# ADC_CPLDV9.net
KiCad netlist of a schematic drawn in EAGLE
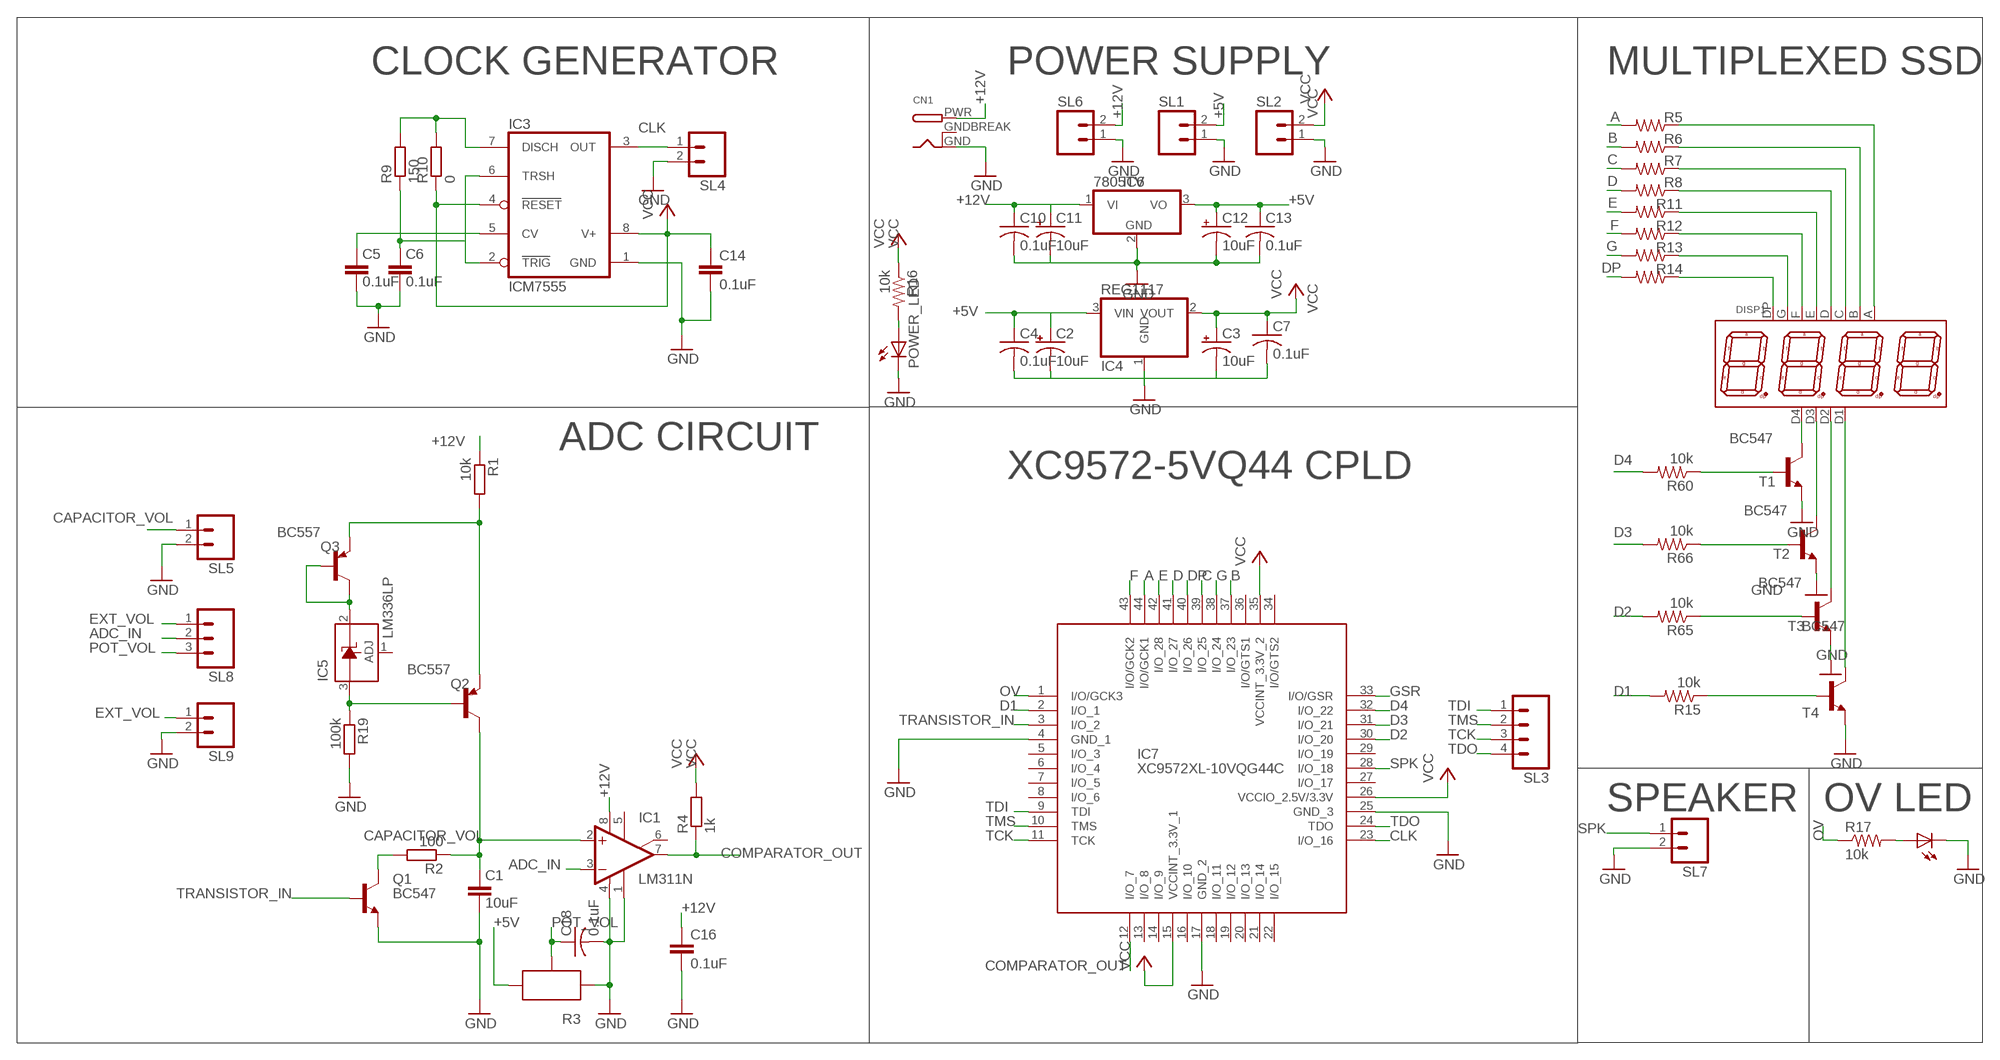
[diagram p0: schematic, sheet 1]

(export (version "E")
  (design (tool "Eeschema 10.0.6"))
  (components
    (comp (ref "C1")
      (value "10uF")
      (footprint "eagle-import:C025-025X050")
      (libsource (lib "eagle-import") (part "C-EU025-025X050"))
    )
    (comp (ref "C2")
      (value "10uF")
      (footprint "eagle-import:B_3528-21R")
      (libsource (lib "eagle-import") (part "CPOL-USB/3528-21R"))
    )
    (comp (ref "C3")
      (value "10uF")
      (footprint "eagle-import:B_3528-21R")
      (libsource (lib "eagle-import") (part "CPOL-USB/3528-21R"))
    )
    (comp (ref "C4")
      (value "0.1uF")
      (footprint "eagle-import:C0805")
      (libsource (lib "eagle-import") (part "C-USC0805"))
    )
    (comp (ref "C5")
      (value "0.1uF")
      (footprint "eagle-import:C025-024X044")
      (libsource (lib "eagle-import") (part "C-EU025-024X044"))
    )
    (comp (ref "C6")
      (value "0.1uF")
      (footprint "eagle-import:C025-024X044")
      (libsource (lib "eagle-import") (part "C-EU025-024X044"))
    )
    (comp (ref "C7")
      (value "0.1uF")
      (footprint "eagle-import:C0805")
      (libsource (lib "eagle-import") (part "C-USC0805"))
    )
    (comp (ref "C10")
      (value "0.1uF")
      (footprint "eagle-import:C0805")
      (libsource (lib "eagle-import") (part "C-USC0805"))
    )
    (comp (ref "C11")
      (value "10uF")
      (footprint "eagle-import:B_3528-21R")
      (libsource (lib "eagle-import") (part "CPOL-USB/3528-21R"))
    )
    (comp (ref "C12")
      (value "10uF")
      (footprint "eagle-import:B_3528-21R")
      (libsource (lib "eagle-import") (part "CPOL-USB/3528-21R"))
    )
    (comp (ref "C13")
      (value "0.1uF")
      (footprint "eagle-import:C0805")
      (libsource (lib "eagle-import") (part "C-USC0805"))
    )
    (comp (ref "C14")
      (value "0.1uF")
      (footprint "eagle-import:C025-025X050")
      (libsource (lib "eagle-import") (part "C-EU025-025X050"))
    )
    (comp (ref "C16")
      (value "0.1uF")
      (footprint "eagle-import:C025-025X050")
      (libsource (lib "eagle-import") (part "C-EU025-025X050"))
    )
    (comp (ref "C18")
      (value "0.1uF")
      (footprint "eagle-import:C0805")
      (libsource (lib "eagle-import") (part "C-USC0805"))
    )
    (comp (ref "CN1")
      (value "DCBARRELPTH")
      (footprint "eagle-import:DCJACK_2MM_PTH")
      (libsource (lib "eagle-import") (part "DCBARRELPTH"))
    )
    (comp (ref "DISP1")
      (value "7-SEG_4D_0.36")
      (footprint "eagle-import:7SEG-4DIG")
      (libsource (lib "eagle-import") (part "7-SEG_4D_0.36"))
    )
    (comp (ref "IC1")
      (value "LM311N")
      (footprint "eagle-import:DIL08")
      (libsource (lib "eagle-import") (part "LM311N"))
    )
    (comp (ref "IC3")
      (value "ICM7555")
      (footprint "eagle-import:DIL08")
      (fields (field (name "MF") "MAXIM") (field (name "MPN") "ICM7555IPA+"))
      (libsource (lib "eagle-import") (part "ICM7555"))
    )
    (comp (ref "IC4")
      (value "REG1117")
      (footprint "eagle-import:SOT223")
      (libsource (lib "eagle-import") (part "REG1117"))
    )
    (comp (ref "IC5")
      (value "LM336LP")
      (footprint "eagle-import:TO92")
      (libsource (lib "eagle-import") (part "LM336LP"))
    )
    (comp (ref "IC6")
      (value "7805TV")
      (footprint "eagle-import:TO220V")
      (libsource (lib "eagle-import") (part "78TV05"))
    )
    (comp (ref "IC7")
      (value "XC9572XL-10VQG44C")
      (footprint "eagle-import:44_PIN_BOB")
      (libsource (lib "eagle-import") (part "XC9572XL-10VQG44C"))
    )
    (comp (ref "POWER_LED")
      (value "LED3MM")
      (footprint "eagle-import:LED3MM")
      (libsource (lib "eagle-import") (part "LED3MM"))
    )
    (comp (ref "POWER_LED1")
      (value "LED3MM")
      (footprint "eagle-import:LED3MM")
      (libsource (lib "eagle-import") (part "LED3MM"))
    )
    (comp (ref "Q1")
      (value "BC547")
      (footprint "eagle-import:TO92")
      (libsource (lib "eagle-import") (part "transistor_402_BC547"))
    )
    (comp (ref "Q2")
      (value "BC557")
      (footprint "eagle-import:TO92")
      (libsource (lib "eagle-import") (part "BC557"))
    )
    (comp (ref "Q3")
      (value "BC557")
      (footprint "eagle-import:TO92")
      (libsource (lib "eagle-import") (part "BC557"))
    )
    (comp (ref "R1")
      (value "10k")
      (footprint "eagle-import:0204_7")
      (libsource (lib "eagle-import") (part "R-EU_0204/7"))
    )
    (comp (ref "R2")
      (value "100")
      (footprint "eagle-import:0204_7")
      (libsource (lib "eagle-import") (part "R-EU_0204/7"))
    )
    (comp (ref "R3")
      (value "POTNORMAL")
      (footprint "eagle-import:RJ9W")
      (libsource (lib "eagle-import") (part "POTNORMAL"))
    )
    (comp (ref "R4")
      (value "1k")
      (footprint "eagle-import:0207_10")
      (libsource (lib "eagle-import") (part "R-EU_0207/10"))
    )
    (comp (ref "R5")
      (value "330")
      (footprint "eagle-import:0207_7")
      (libsource (lib "eagle-import") (part "R-US_0207/7"))
    )
    (comp (ref "R6")
      (value "330")
      (footprint "eagle-import:0207_7")
      (libsource (lib "eagle-import") (part "R-US_0207/7"))
    )
    (comp (ref "R7")
      (value "330")
      (footprint "eagle-import:0207_7")
      (libsource (lib "eagle-import") (part "R-US_0207/7"))
    )
    (comp (ref "R8")
      (value "1k")
      (footprint "eagle-import:0207_7")
      (libsource (lib "eagle-import") (part "R-US_0207/7"))
    )
    (comp (ref "R9")
      (value "150")
      (footprint "eagle-import:0204_7")
      (libsource (lib "eagle-import") (part "R-EU_0204/7"))
    )
    (comp (ref "R10")
      (value "0")
      (footprint "eagle-import:0204_7")
      (libsource (lib "eagle-import") (part "R-EU_0204/7"))
    )
    (comp (ref "R11")
      (value "330")
      (footprint "eagle-import:0207_7")
      (libsource (lib "eagle-import") (part "R-US_0207/7"))
    )
    (comp (ref "R12")
      (value "330")
      (footprint "eagle-import:0207_7")
      (libsource (lib "eagle-import") (part "R-US_0207/7"))
    )
    (comp (ref "R13")
      (value "330")
      (footprint "eagle-import:0207_7")
      (libsource (lib "eagle-import") (part "R-US_0207/7"))
    )
    (comp (ref "R14")
      (value "330")
      (footprint "eagle-import:0207_7")
      (libsource (lib "eagle-import") (part "R-US_0207/7"))
    )
    (comp (ref "R15")
      (value "10k")
      (footprint "eagle-import:0207_7")
      (libsource (lib "eagle-import") (part "R-US_0207/7"))
    )
    (comp (ref "R16")
      (value "10k")
      (footprint "eagle-import:0207_7")
      (libsource (lib "eagle-import") (part "R-US_0207/7"))
    )
    (comp (ref "R17")
      (value "10k")
      (footprint "eagle-import:0207_7")
      (libsource (lib "eagle-import") (part "R-US_0207/7"))
    )
    (comp (ref "R19")
      (value "100k")
      (footprint "eagle-import:0204_7")
      (libsource (lib "eagle-import") (part "R-EU_0204/7"))
    )
    (comp (ref "R60")
      (value "10k")
      (footprint "eagle-import:0207_7")
      (libsource (lib "eagle-import") (part "R-US_0207/7"))
    )
    (comp (ref "R65")
      (value "10k")
      (footprint "eagle-import:0207_7")
      (libsource (lib "eagle-import") (part "R-US_0207/7"))
    )
    (comp (ref "R66")
      (value "10k")
      (footprint "eagle-import:0207_7")
      (libsource (lib "eagle-import") (part "R-US_0207/7"))
    )
    (comp (ref "SL1")
      (value "M02")
      (footprint "eagle-import:02P")
      (libsource (lib "eagle-import") (part "M02"))
    )
    (comp (ref "SL2")
      (value "M02")
      (footprint "eagle-import:02P")
      (libsource (lib "eagle-import") (part "M02"))
    )
    (comp (ref "SL3")
      (value "M04")
      (footprint "eagle-import:04P")
      (libsource (lib "eagle-import") (part "M04"))
    )
    (comp (ref "SL4")
      (value "M02")
      (footprint "eagle-import:02P")
      (libsource (lib "eagle-import") (part "M02"))
    )
    (comp (ref "SL5")
      (value "M02")
      (footprint "eagle-import:02P")
      (libsource (lib "eagle-import") (part "M02"))
    )
    (comp (ref "SL6")
      (value "M02")
      (footprint "eagle-import:02P")
      (libsource (lib "eagle-import") (part "M02"))
    )
    (comp (ref "SL7")
      (value "M02")
      (footprint "eagle-import:02P")
      (libsource (lib "eagle-import") (part "M02"))
    )
    (comp (ref "SL8")
      (value "M03")
      (footprint "eagle-import:03P")
      (libsource (lib "eagle-import") (part "M03"))
    )
    (comp (ref "SL9")
      (value "M02")
      (footprint "eagle-import:02P")
      (libsource (lib "eagle-import") (part "M02"))
    )
    (comp (ref "T1")
      (value "BC547")
      (footprint "eagle-import:TO92")
      (libsource (lib "eagle-import") (part "BC547"))
    )
    (comp (ref "T2")
      (value "BC547")
      (footprint "eagle-import:TO92")
      (libsource (lib "eagle-import") (part "BC547"))
    )
    (comp (ref "T3")
      (value "BC547")
      (footprint "eagle-import:TO92")
      (libsource (lib "eagle-import") (part "BC547"))
    )
    (comp (ref "T4")
      (value "BC547")
      (footprint "eagle-import:TO92")
      (libsource (lib "eagle-import") (part "BC547"))
    )
  )
  (nets
    (net (code "1") (name "/+5V") (class "Default")
      (node (ref "C12") (pin "+") (pinfunction "+_+") (pintype "passive"))
      (node (ref "C13") (pin "1") (pinfunction "1_1") (pintype "passive"))
      (node (ref "C2") (pin "+") (pinfunction "+_+") (pintype "passive"))
      (node (ref "C4") (pin "1") (pinfunction "1_1") (pintype "passive"))
      (node (ref "IC4") (pin "3") (pinfunction "VIN_3") (pintype "input"))
      (node (ref "IC6") (pin "3") (pinfunction "VO_3") (pintype "passive"))
      (node (ref "R3") (pin "A") (pinfunction "A_A") (pintype "passive"))
      (node (ref "SL1") (pin "2") (pinfunction "2_2") (pintype "passive"))
    )
    (net (code "2") (name "/+12V") (class "Default")
      (node (ref "C10") (pin "1") (pinfunction "1_1") (pintype "passive"))
      (node (ref "C11") (pin "+") (pinfunction "+_+") (pintype "passive"))
      (node (ref "C16") (pin "1") (pinfunction "1_1") (pintype "passive"))
      (node (ref "CN1") (pin "PWR") (pinfunction "PWR_PWR") (pintype "power_in"))
      (node (ref "IC1") (pin "8") (pinfunction "V+_8") (pintype "power_in"))
      (node (ref "IC6") (pin "1") (pinfunction "VI_1") (pintype "input"))
      (node (ref "R1") (pin "1") (pinfunction "1_1") (pintype "passive"))
      (node (ref "SL6") (pin "2") (pinfunction "2_2") (pintype "passive"))
    )
    (net (code "3") (name "/A") (class "Default")
      (node (ref "IC7") (pin "44") (pinfunction "I/O/GCK1_44") (pintype "bidirectional"))
      (node (ref "R5") (pin "2") (pinfunction "2_2") (pintype "passive"))
    )
    (net (code "4") (name "/ADC_IN") (class "Default")
      (node (ref "IC1") (pin "3") (pinfunction "-IN_3") (pintype "input"))
      (node (ref "SL8") (pin "2") (pinfunction "2_2") (pintype "passive"))
    )
    (net (code "5") (name "/B") (class "Default")
      (node (ref "IC7") (pin "37") (pinfunction "I/O_23_37") (pintype "bidirectional"))
      (node (ref "R6") (pin "2") (pinfunction "2_2") (pintype "passive"))
    )
    (net (code "6") (name "/C") (class "Default")
      (node (ref "IC7") (pin "39") (pinfunction "I/O_25_39") (pintype "bidirectional"))
      (node (ref "R7") (pin "2") (pinfunction "2_2") (pintype "passive"))
    )
    (net (code "7") (name "/CAPACITOR_VOL") (class "Default")
      (node (ref "C1") (pin "1") (pinfunction "1_1") (pintype "passive"))
      (node (ref "IC1") (pin "2") (pinfunction "+IN_2") (pintype "input"))
      (node (ref "Q2") (pin "3") (pinfunction "C_3") (pintype "passive"))
      (node (ref "R2") (pin "1") (pinfunction "1_1") (pintype "passive"))
      (node (ref "SL5") (pin "1") (pinfunction "1_1") (pintype "passive"))
    )
    (net (code "8") (name "/CLK") (class "Default")
      (node (ref "IC3") (pin "3") (pinfunction "OUT_3") (pintype "output"))
      (node (ref "IC7") (pin "23") (pinfunction "I/O_16_23") (pintype "bidirectional"))
      (node (ref "SL4") (pin "1") (pinfunction "1_1") (pintype "passive"))
    )
    (net (code "9") (name "/COMPARATOR_OUT") (class "Default")
      (node (ref "IC1") (pin "7") (pinfunction "OUT_7") (pintype "output"))
      (node (ref "IC7") (pin "12") (pinfunction "I/O_7_12") (pintype "bidirectional"))
      (node (ref "R4") (pin "1") (pinfunction "1_1") (pintype "passive"))
    )
    (net (code "10") (name "/D") (class "Default")
      (node (ref "IC7") (pin "41") (pinfunction "I/O_27_41") (pintype "bidirectional"))
      (node (ref "R8") (pin "2") (pinfunction "2_2") (pintype "passive"))
    )
    (net (code "11") (name "/D1") (class "Default")
      (node (ref "IC7") (pin "2") (pinfunction "I/O_1_2") (pintype "bidirectional"))
      (node (ref "R15") (pin "2") (pinfunction "2_2") (pintype "passive"))
    )
    (net (code "12") (name "/D2") (class "Default")
      (node (ref "IC7") (pin "30") (pinfunction "I/O_20_30") (pintype "bidirectional"))
      (node (ref "R65") (pin "2") (pinfunction "2_2") (pintype "passive"))
    )
    (net (code "13") (name "/D3") (class "Default")
      (node (ref "IC7") (pin "31") (pinfunction "I/O_21_31") (pintype "bidirectional"))
      (node (ref "R66") (pin "2") (pinfunction "2_2") (pintype "passive"))
    )
    (net (code "14") (name "/D4") (class "Default")
      (node (ref "IC7") (pin "32") (pinfunction "I/O_22_32") (pintype "bidirectional"))
      (node (ref "R60") (pin "2") (pinfunction "2_2") (pintype "passive"))
    )
    (net (code "15") (name "/DP") (class "Default")
      (node (ref "IC7") (pin "40") (pinfunction "I/O_26_40") (pintype "bidirectional"))
      (node (ref "R14") (pin "2") (pinfunction "2_2") (pintype "passive"))
    )
    (net (code "16") (name "/E") (class "Default")
      (node (ref "IC7") (pin "42") (pinfunction "I/O_28_42") (pintype "bidirectional"))
      (node (ref "R11") (pin "2") (pinfunction "2_2") (pintype "passive"))
    )
    (net (code "17") (name "/EXT_VOL") (class "Default")
      (node (ref "SL8") (pin "1") (pinfunction "1_1") (pintype "passive"))
      (node (ref "SL9") (pin "1") (pinfunction "1_1") (pintype "passive"))
    )
    (net (code "18") (name "/F") (class "Default")
      (node (ref "IC7") (pin "43") (pinfunction "I/O/GCK2_43") (pintype "bidirectional"))
      (node (ref "R12") (pin "2") (pinfunction "2_2") (pintype "passive"))
    )
    (net (code "19") (name "/G") (class "Default")
      (node (ref "IC7") (pin "38") (pinfunction "I/O_24_38") (pintype "bidirectional"))
      (node (ref "R13") (pin "2") (pinfunction "2_2") (pintype "passive"))
    )
    (net (code "20") (name "/GNDBREAK") (class "Default")
      (node (ref "CN1") (pin "GNDBREAK") (pinfunction "GNDBREAK_GNDBREAK") (pintype "power_in"))
    )
    (net (code "21") (name "/GSR") (class "Default")
      (node (ref "IC7") (pin "33") (pinfunction "I/O/GSR_33") (pintype "bidirectional"))
    )
    (net (code "22") (name "/OV") (class "Default")
      (node (ref "IC7") (pin "1") (pinfunction "I/O/GCK3_1") (pintype "bidirectional"))
      (node (ref "R17") (pin "1") (pinfunction "1_1") (pintype "passive"))
    )
    (net (code "23") (name "/POT_VOL") (class "Default")
      (node (ref "C18") (pin "1") (pinfunction "1_1") (pintype "passive"))
      (node (ref "R3") (pin "S") (pinfunction "S_S") (pintype "passive"))
      (node (ref "SL8") (pin "3") (pinfunction "3_3") (pintype "passive"))
    )
    (net (code "24") (name "/SPK") (class "Default")
      (node (ref "IC7") (pin "28") (pinfunction "I/O_18_28") (pintype "bidirectional"))
      (node (ref "SL7") (pin "1") (pinfunction "1_1") (pintype "passive"))
    )
    (net (code "25") (name "/TCK") (class "Default")
      (node (ref "IC7") (pin "11") (pinfunction "TCK_11") (pintype "bidirectional"))
      (node (ref "SL3") (pin "3") (pinfunction "3_3") (pintype "passive"))
    )
    (net (code "26") (name "/TDI") (class "Default")
      (node (ref "IC7") (pin "9") (pinfunction "TDI_9") (pintype "input"))
      (node (ref "SL3") (pin "1") (pinfunction "1_1") (pintype "passive"))
    )
    (net (code "27") (name "/TDO") (class "Default")
      (node (ref "IC7") (pin "24") (pinfunction "TDO_24") (pintype "output"))
      (node (ref "SL3") (pin "4") (pinfunction "4_4") (pintype "passive"))
    )
    (net (code "28") (name "/TMS") (class "Default")
      (node (ref "IC7") (pin "10") (pinfunction "TMS_10") (pintype "bidirectional"))
      (node (ref "SL3") (pin "2") (pinfunction "2_2") (pintype "passive"))
    )
    (net (code "29") (name "/TRANSISTOR_IN") (class "Default")
      (node (ref "IC7") (pin "3") (pinfunction "I/O_2_3") (pintype "bidirectional"))
      (node (ref "Q1") (pin "2") (pinfunction "B_2") (pintype "passive"))
    )
    (net (code "30") (name "GND") (class "Default")
      (node (ref "C1") (pin "2") (pinfunction "2_2") (pintype "passive"))
      (node (ref "C10") (pin "2") (pinfunction "2_2") (pintype "passive"))
      (node (ref "C11") (pin "-") (pinfunction "-_-") (pintype "passive"))
      (node (ref "C12") (pin "-") (pinfunction "-_-") (pintype "passive"))
      (node (ref "C13") (pin "2") (pinfunction "2_2") (pintype "passive"))
      (node (ref "C14") (pin "2") (pinfunction "2_2") (pintype "passive"))
      (node (ref "C16") (pin "2") (pinfunction "2_2") (pintype "passive"))
      (node (ref "C18") (pin "2") (pinfunction "2_2") (pintype "passive"))
      (node (ref "C2") (pin "-") (pinfunction "-_-") (pintype "passive"))
      (node (ref "C3") (pin "-") (pinfunction "-_-") (pintype "passive"))
      (node (ref "C4") (pin "2") (pinfunction "2_2") (pintype "passive"))
      (node (ref "C5") (pin "2") (pinfunction "2_2") (pintype "passive"))
      (node (ref "C6") (pin "2") (pinfunction "2_2") (pintype "passive"))
      (node (ref "C7") (pin "2") (pinfunction "2_2") (pintype "passive"))
      (node (ref "CN1") (pin "GND") (pinfunction "GND_GND") (pintype "power_in"))
      (node (ref "IC1") (pin "1") (pinfunction "GND_1") (pintype "passive"))
      (node (ref "IC1") (pin "4") (pinfunction "V-_4") (pintype "power_in"))
      (node (ref "IC3") (pin "1") (pinfunction "GND_1") (pintype "power_in"))
      (node (ref "IC4") (pin "1") (pinfunction "GND_1") (pintype "power_in"))
      (node (ref "IC6") (pin "2") (pinfunction "GND_2") (pintype "passive"))
      (node (ref "IC7") (pin "17") (pinfunction "GND_2_17") (pintype "power_in"))
      (node (ref "IC7") (pin "25") (pinfunction "GND_3_25") (pintype "power_in"))
      (node (ref "IC7") (pin "4") (pinfunction "GND_1_4") (pintype "power_in"))
      (node (ref "POWER_LED") (pin "K") (pinfunction "C_K") (pintype "passive"))
      (node (ref "POWER_LED1") (pin "K") (pinfunction "C_K") (pintype "passive"))
      (node (ref "Q1") (pin "1") (pinfunction "E_1") (pintype "passive"))
      (node (ref "R19") (pin "2") (pinfunction "2_2") (pintype "passive"))
      (node (ref "R3") (pin "E") (pinfunction "E_E") (pintype "passive"))
      (node (ref "SL1") (pin "1") (pinfunction "1_1") (pintype "passive"))
      (node (ref "SL2") (pin "1") (pinfunction "1_1") (pintype "passive"))
      (node (ref "SL4") (pin "2") (pinfunction "2_2") (pintype "passive"))
      (node (ref "SL5") (pin "2") (pinfunction "2_2") (pintype "passive"))
      (node (ref "SL6") (pin "1") (pinfunction "1_1") (pintype "passive"))
      (node (ref "SL7") (pin "2") (pinfunction "2_2") (pintype "passive"))
      (node (ref "SL9") (pin "2") (pinfunction "2_2") (pintype "passive"))
      (node (ref "T1") (pin "1") (pinfunction "E_1") (pintype "passive"))
      (node (ref "T2") (pin "1") (pinfunction "E_1") (pintype "passive"))
      (node (ref "T3") (pin "1") (pinfunction "E_1") (pintype "passive"))
      (node (ref "T4") (pin "1") (pinfunction "E_1") (pintype "passive"))
    )
    (net (code "31") (name "Net-(DISP1-PadA)") (class "Default")
      (node (ref "DISP1") (pin "A") (pinfunction "A_A") (pintype "bidirectional"))
      (node (ref "R5") (pin "1") (pinfunction "1_1") (pintype "passive"))
    )
    (net (code "32") (name "Net-(DISP1-PadB)") (class "Default")
      (node (ref "DISP1") (pin "B") (pinfunction "B_B") (pintype "bidirectional"))
      (node (ref "R6") (pin "1") (pinfunction "1_1") (pintype "passive"))
    )
    (net (code "33") (name "Net-(DISP1-PadC)") (class "Default")
      (node (ref "DISP1") (pin "C") (pinfunction "C_C") (pintype "bidirectional"))
      (node (ref "R7") (pin "1") (pinfunction "1_1") (pintype "passive"))
    )
    (net (code "34") (name "Net-(DISP1-PadD)") (class "Default")
      (node (ref "DISP1") (pin "D") (pinfunction "D_D") (pintype "bidirectional"))
      (node (ref "R8") (pin "1") (pinfunction "1_1") (pintype "passive"))
    )
    (net (code "35") (name "Net-(DISP1-PadDP)") (class "Default")
      (node (ref "DISP1") (pin "DP") (pinfunction "DP_DP") (pintype "bidirectional"))
      (node (ref "R14") (pin "1") (pinfunction "1_1") (pintype "passive"))
    )
    (net (code "36") (name "Net-(DISP1-PadE)") (class "Default")
      (node (ref "DISP1") (pin "E") (pinfunction "E_E") (pintype "bidirectional"))
      (node (ref "R11") (pin "1") (pinfunction "1_1") (pintype "passive"))
    )
    (net (code "37") (name "Net-(DISP1-PadF)") (class "Default")
      (node (ref "DISP1") (pin "F") (pinfunction "F_F") (pintype "bidirectional"))
      (node (ref "R12") (pin "1") (pinfunction "1_1") (pintype "passive"))
    )
    (net (code "38") (name "Net-(DISP1-PadG)") (class "Default")
      (node (ref "DISP1") (pin "G") (pinfunction "G_G") (pintype "bidirectional"))
      (node (ref "R13") (pin "1") (pinfunction "1_1") (pintype "passive"))
    )
    (net (code "39") (name "Net-(IC3-CV)") (class "Default")
      (node (ref "C5") (pin "1") (pinfunction "1_1") (pintype "passive"))
      (node (ref "IC3") (pin "5") (pinfunction "CV_5") (pintype "passive"))
    )
    (net (code "40") (name "Net-(IC3-DISCH)") (class "Default")
      (node (ref "IC3") (pin "7") (pinfunction "DISCH_7") (pintype "input"))
      (node (ref "R10") (pin "2") (pinfunction "2_2") (pintype "passive"))
      (node (ref "R9") (pin "2") (pinfunction "2_2") (pintype "passive"))
    )
    (net (code "41") (name "Net-(IC3-TRIG)") (class "Default")
      (node (ref "C6") (pin "1") (pinfunction "1_1") (pintype "passive"))
      (node (ref "IC3") (pin "2") (pinfunction "TRIG_2") (pintype "bidirectional"))
      (node (ref "IC3") (pin "6") (pinfunction "TRSH_6") (pintype "input"))
      (node (ref "R9") (pin "1") (pinfunction "1_1") (pintype "passive"))
    )
    (net (code "42") (name "Net-(IC5-A)") (class "Default")
      (node (ref "IC5") (pin "3") (pinfunction "A_3") (pintype "input"))
      (node (ref "Q2") (pin "2") (pinfunction "B_2") (pintype "passive"))
      (node (ref "R19") (pin "1") (pinfunction "1_1") (pintype "passive"))
    )
    (net (code "43") (name "Net-(IC5-C)") (class "Default")
      (node (ref "IC5") (pin "2") (pinfunction "C_2") (pintype "passive"))
      (node (ref "Q3") (pin "2") (pinfunction "B_2") (pintype "passive"))
      (node (ref "Q3") (pin "3") (pinfunction "C_3") (pintype "passive"))
    )
    (net (code "44") (name "Net-(POWER_LED-PadA)") (class "Default")
      (node (ref "POWER_LED") (pin "A") (pinfunction "A_A") (pintype "passive"))
      (node (ref "R16") (pin "2") (pinfunction "2_2") (pintype "passive"))
    )
    (net (code "45") (name "Net-(POWER_LED1-PadA)") (class "Default")
      (node (ref "POWER_LED1") (pin "A") (pinfunction "A_A") (pintype "passive"))
      (node (ref "R17") (pin "2") (pinfunction "2_2") (pintype "passive"))
    )
    (net (code "46") (name "Net-(Q1-C)") (class "Default")
      (node (ref "Q1") (pin "3") (pinfunction "C_3") (pintype "passive"))
      (node (ref "R2") (pin "2") (pinfunction "2_2") (pintype "passive"))
    )
    (net (code "47") (name "Net-(Q2-E)") (class "Default")
      (node (ref "Q2") (pin "1") (pinfunction "E_1") (pintype "passive"))
      (node (ref "Q3") (pin "1") (pinfunction "E_1") (pintype "passive"))
      (node (ref "R1") (pin "2") (pinfunction "2_2") (pintype "passive"))
    )
    (net (code "48") (name "Net-(T1-B)") (class "Default")
      (node (ref "R60") (pin "1") (pinfunction "1_1") (pintype "passive"))
      (node (ref "T1") (pin "2") (pinfunction "B_2") (pintype "passive"))
    )
    (net (code "49") (name "Net-(T1-C)") (class "Default")
      (node (ref "DISP1") (pin "D4") (pinfunction "D4_D4") (pintype "bidirectional"))
      (node (ref "T1") (pin "3") (pinfunction "C_3") (pintype "passive"))
    )
    (net (code "50") (name "Net-(T2-B)") (class "Default")
      (node (ref "R66") (pin "1") (pinfunction "1_1") (pintype "passive"))
      (node (ref "T2") (pin "2") (pinfunction "B_2") (pintype "passive"))
    )
    (net (code "51") (name "Net-(T2-C)") (class "Default")
      (node (ref "DISP1") (pin "D3") (pinfunction "D3_D3") (pintype "bidirectional"))
      (node (ref "T2") (pin "3") (pinfunction "C_3") (pintype "passive"))
    )
    (net (code "52") (name "Net-(T3-B)") (class "Default")
      (node (ref "R65") (pin "1") (pinfunction "1_1") (pintype "passive"))
      (node (ref "T3") (pin "2") (pinfunction "B_2") (pintype "passive"))
    )
    (net (code "53") (name "Net-(T3-C)") (class "Default")
      (node (ref "DISP1") (pin "D2") (pinfunction "D2_D2") (pintype "bidirectional"))
      (node (ref "T3") (pin "3") (pinfunction "C_3") (pintype "passive"))
    )
    (net (code "54") (name "Net-(T4-B)") (class "Default")
      (node (ref "R15") (pin "1") (pinfunction "1_1") (pintype "passive"))
      (node (ref "T4") (pin "2") (pinfunction "B_2") (pintype "passive"))
    )
    (net (code "55") (name "Net-(T4-C)") (class "Default")
      (node (ref "DISP1") (pin "D1") (pinfunction "D1_D1") (pintype "bidirectional"))
      (node (ref "T4") (pin "3") (pinfunction "C_3") (pintype "passive"))
    )
    (net (code "56") (name "VCC") (class "Default")
      (node (ref "C14") (pin "1") (pinfunction "1_1") (pintype "passive"))
      (node (ref "C3") (pin "+") (pinfunction "+_+") (pintype "passive"))
      (node (ref "C7") (pin "1") (pinfunction "1_1") (pintype "passive"))
      (node (ref "IC3") (pin "4") (pinfunction "RESET_4") (pintype "input"))
      (node (ref "IC3") (pin "8") (pinfunction "V+_8") (pintype "power_in"))
      (node (ref "IC4") (pin "2") (pinfunction "VOUT_2") (pintype "output"))
      (node (ref "IC7") (pin "15") (pinfunction "VCCINT_3.3V_1_15") (pintype "power_in"))
      (node (ref "IC7") (pin "26") (pinfunction "VCCIO_2.5V/3.3V_26") (pintype "power_in"))
      (node (ref "IC7") (pin "35") (pinfunction "VCCINT_3.3V_2_35") (pintype "power_in"))
      (node (ref "R10") (pin "1") (pinfunction "1_1") (pintype "passive"))
      (node (ref "R16") (pin "1") (pinfunction "1_1") (pintype "passive"))
      (node (ref "R4") (pin "2") (pinfunction "2_2") (pintype "passive"))
      (node (ref "SL2") (pin "2") (pinfunction "2_2") (pintype "passive"))
    )
    (net (code "57") (name "unconnected-(IC1-ON-Pad5)") (class "Default")
      (node (ref "IC1") (pin "5") (pinfunction "ON_5") (pintype "passive"))
    )
    (net (code "58") (name "unconnected-(IC1-ON{slash}STR-Pad6)") (class "Default")
      (node (ref "IC1") (pin "6") (pinfunction "ON/STR_6") (pintype "passive"))
    )
    (net (code "59") (name "unconnected-(IC5-ADJ-Pad1)") (class "Default")
      (node (ref "IC5") (pin "1") (pinfunction "ADJ_1") (pintype "input"))
    )
    (net (code "60") (name "unconnected-(IC7-I{slash}O_3-Pad5)") (class "Default")
      (node (ref "IC7") (pin "5") (pinfunction "I/O_3_5") (pintype "bidirectional"))
    )
    (net (code "61") (name "unconnected-(IC7-I{slash}O_4-Pad6)") (class "Default")
      (node (ref "IC7") (pin "6") (pinfunction "I/O_4_6") (pintype "bidirectional"))
    )
    (net (code "62") (name "unconnected-(IC7-I{slash}O_5-Pad7)") (class "Default")
      (node (ref "IC7") (pin "7") (pinfunction "I/O_5_7") (pintype "bidirectional"))
    )
    (net (code "63") (name "unconnected-(IC7-I{slash}O_6-Pad8)") (class "Default")
      (node (ref "IC7") (pin "8") (pinfunction "I/O_6_8") (pintype "bidirectional"))
    )
    (net (code "64") (name "unconnected-(IC7-I{slash}O_8-Pad13)") (class "Default")
      (node (ref "IC7") (pin "13") (pinfunction "I/O_8_13") (pintype "bidirectional"))
    )
    (net (code "65") (name "unconnected-(IC7-I{slash}O_9-Pad14)") (class "Default")
      (node (ref "IC7") (pin "14") (pinfunction "I/O_9_14") (pintype "bidirectional"))
    )
    (net (code "66") (name "unconnected-(IC7-I{slash}O_10-Pad16)") (class "Default")
      (node (ref "IC7") (pin "16") (pinfunction "I/O_10_16") (pintype "bidirectional"))
    )
    (net (code "67") (name "unconnected-(IC7-I{slash}O_11-Pad18)") (class "Default")
      (node (ref "IC7") (pin "18") (pinfunction "I/O_11_18") (pintype "bidirectional"))
    )
    (net (code "68") (name "unconnected-(IC7-I{slash}O_12-Pad19)") (class "Default")
      (node (ref "IC7") (pin "19") (pinfunction "I/O_12_19") (pintype "bidirectional"))
    )
    (net (code "69") (name "unconnected-(IC7-I{slash}O_13-Pad20)") (class "Default")
      (node (ref "IC7") (pin "20") (pinfunction "I/O_13_20") (pintype "bidirectional"))
    )
    (net (code "70") (name "unconnected-(IC7-I{slash}O_14-Pad21)") (class "Default")
      (node (ref "IC7") (pin "21") (pinfunction "I/O_14_21") (pintype "bidirectional"))
    )
    (net (code "71") (name "unconnected-(IC7-I{slash}O_15-Pad22)") (class "Default")
      (node (ref "IC7") (pin "22") (pinfunction "I/O_15_22") (pintype "bidirectional"))
    )
    (net (code "72") (name "unconnected-(IC7-I{slash}O_17-Pad27)") (class "Default")
      (node (ref "IC7") (pin "27") (pinfunction "I/O_17_27") (pintype "bidirectional"))
    )
    (net (code "73") (name "unconnected-(IC7-I{slash}O_19-Pad29)") (class "Default")
      (node (ref "IC7") (pin "29") (pinfunction "I/O_19_29") (pintype "bidirectional"))
    )
    (net (code "74") (name "unconnected-(IC7-I{slash}O{slash}GTS1-Pad36)") (class "Default")
      (node (ref "IC7") (pin "36") (pinfunction "I/O/GTS1_36") (pintype "bidirectional"))
    )
    (net (code "75") (name "unconnected-(IC7-I{slash}O{slash}GTS2-Pad34)") (class "Default")
      (node (ref "IC7") (pin "34") (pinfunction "I/O/GTS2_34") (pintype "bidirectional"))
    )
  )
)
